# tmc2209.net
KiCad netlist of a schematic drawn in EAGLE
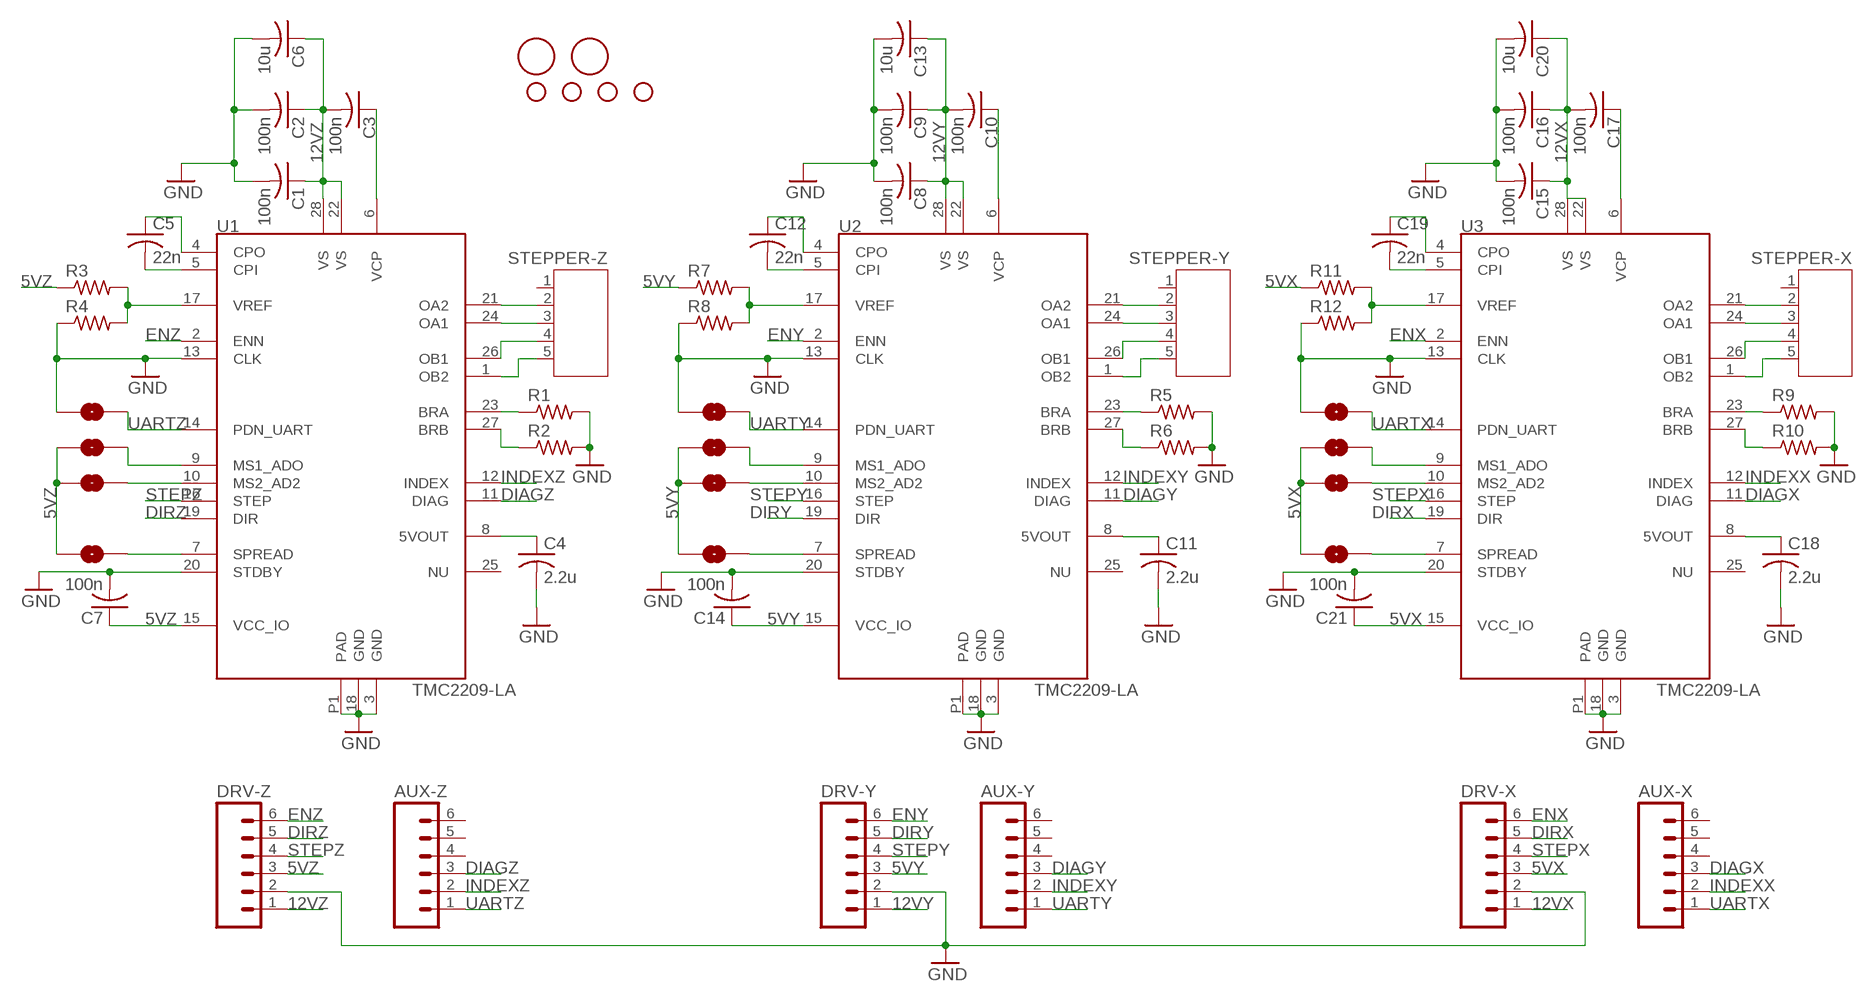
[diagram p0: schematic, sheet 1]

(export (version "E")
  (design (tool "Eeschema 10.0.6"))
  (components
    (comp (ref "AUX-X")
      (value "M06LOCK")
      (footprint "eagle-import:1X06_LOCK")
      (libsource (lib "eagle-import") (part "M06LOCK"))
    )
    (comp (ref "AUX-Y")
      (value "M06LOCK")
      (footprint "eagle-import:1X06_LOCK")
      (libsource (lib "eagle-import") (part "M06LOCK"))
    )
    (comp (ref "AUX-Z")
      (value "M06LOCK")
      (footprint "eagle-import:1X06_LOCK")
      (libsource (lib "eagle-import") (part "M06LOCK"))
    )
    (comp (ref "C1")
      (value "100n")
      (footprint "eagle-import:C0603")
      (libsource (lib "eagle-import") (part "C-USC0603"))
    )
    (comp (ref "C2")
      (value "100n")
      (footprint "eagle-import:C0603")
      (libsource (lib "eagle-import") (part "C-USC0603"))
    )
    (comp (ref "C3")
      (value "100n")
      (footprint "eagle-import:C0603")
      (libsource (lib "eagle-import") (part "C-USC0603"))
    )
    (comp (ref "C4")
      (value "2.2u")
      (footprint "eagle-import:C1206")
      (libsource (lib "eagle-import") (part "C-USC1206"))
    )
    (comp (ref "C5")
      (value "22n")
      (footprint "eagle-import:C0603")
      (libsource (lib "eagle-import") (part "C-USC0603"))
    )
    (comp (ref "C6")
      (value "10u")
      (footprint "eagle-import:C1206")
      (libsource (lib "eagle-import") (part "C-USC1206"))
    )
    (comp (ref "C7")
      (value "100n")
      (footprint "eagle-import:C0603")
      (libsource (lib "eagle-import") (part "C-USC0603"))
    )
    (comp (ref "C8")
      (value "100n")
      (footprint "eagle-import:C0603")
      (libsource (lib "eagle-import") (part "C-USC0603"))
    )
    (comp (ref "C9")
      (value "100n")
      (footprint "eagle-import:C0603")
      (libsource (lib "eagle-import") (part "C-USC0603"))
    )
    (comp (ref "C10")
      (value "100n")
      (footprint "eagle-import:C0603")
      (libsource (lib "eagle-import") (part "C-USC0603"))
    )
    (comp (ref "C11")
      (value "2.2u")
      (footprint "eagle-import:C1206")
      (libsource (lib "eagle-import") (part "C-USC1206"))
    )
    (comp (ref "C12")
      (value "22n")
      (footprint "eagle-import:C0603")
      (libsource (lib "eagle-import") (part "C-USC0603"))
    )
    (comp (ref "C13")
      (value "10u")
      (footprint "eagle-import:C1206")
      (libsource (lib "eagle-import") (part "C-USC1206"))
    )
    (comp (ref "C14")
      (value "100n")
      (footprint "eagle-import:C0603")
      (libsource (lib "eagle-import") (part "C-USC0603"))
    )
    (comp (ref "C15")
      (value "100n")
      (footprint "eagle-import:C0603")
      (libsource (lib "eagle-import") (part "C-USC0603"))
    )
    (comp (ref "C16")
      (value "100n")
      (footprint "eagle-import:C0603")
      (libsource (lib "eagle-import") (part "C-USC0603"))
    )
    (comp (ref "C17")
      (value "100n")
      (footprint "eagle-import:C0603")
      (libsource (lib "eagle-import") (part "C-USC0603"))
    )
    (comp (ref "C18")
      (value "2.2u")
      (footprint "eagle-import:C1206")
      (libsource (lib "eagle-import") (part "C-USC1206"))
    )
    (comp (ref "C19")
      (value "22n")
      (footprint "eagle-import:C0603")
      (libsource (lib "eagle-import") (part "C-USC0603"))
    )
    (comp (ref "C20")
      (value "10u")
      (footprint "eagle-import:C1206")
      (libsource (lib "eagle-import") (part "C-USC1206"))
    )
    (comp (ref "C21")
      (value "100n")
      (footprint "eagle-import:C0603")
      (libsource (lib "eagle-import") (part "C-USC0603"))
    )
    (comp (ref "DRV-X")
      (value "M06LOCK")
      (footprint "eagle-import:1X06_LOCK")
      (libsource (lib "eagle-import") (part "M06LOCK"))
    )
    (comp (ref "DRV-Y")
      (value "M06LOCK")
      (footprint "eagle-import:1X06_LOCK")
      (libsource (lib "eagle-import") (part "M06LOCK"))
    )
    (comp (ref "DRV-Z")
      (value "M06LOCK")
      (footprint "eagle-import:1X06_LOCK")
      (libsource (lib "eagle-import") (part "M06LOCK"))
    )
    (comp (ref "PDX")
      (value "SOLDERJUMPERNO")
      (footprint "eagle-import:SJ_2S-NO")
      (libsource (lib "eagle-import") (part "SOLDERJUMPERNO"))
    )
    (comp (ref "PDY")
      (value "SOLDERJUMPERNO")
      (footprint "eagle-import:SJ_2S-NO")
      (libsource (lib "eagle-import") (part "SOLDERJUMPERNO"))
    )
    (comp (ref "PDZ")
      (value "SOLDERJUMPERNO")
      (footprint "eagle-import:SJ_2S-NO")
      (libsource (lib "eagle-import") (part "SOLDERJUMPERNO"))
    )
    (comp (ref "R1")
      (value "R-US_R0805")
      (footprint "eagle-import:R0805")
      (libsource (lib "eagle-import") (part "R-US_R0805"))
    )
    (comp (ref "R2")
      (value "R-US_R0805")
      (footprint "eagle-import:R0805")
      (libsource (lib "eagle-import") (part "R-US_R0805"))
    )
    (comp (ref "R3")
      (value "R-US_R0603")
      (footprint "eagle-import:R0603")
      (libsource (lib "eagle-import") (part "R-US_R0603"))
    )
    (comp (ref "R4")
      (value "R-US_R0603")
      (footprint "eagle-import:R0603")
      (libsource (lib "eagle-import") (part "R-US_R0603"))
    )
    (comp (ref "R5")
      (value "R-US_R0805")
      (footprint "eagle-import:R0805")
      (libsource (lib "eagle-import") (part "R-US_R0805"))
    )
    (comp (ref "R6")
      (value "R-US_R0805")
      (footprint "eagle-import:R0805")
      (libsource (lib "eagle-import") (part "R-US_R0805"))
    )
    (comp (ref "R7")
      (value "R-US_R0603")
      (footprint "eagle-import:R0603")
      (libsource (lib "eagle-import") (part "R-US_R0603"))
    )
    (comp (ref "R8")
      (value "R-US_R0603")
      (footprint "eagle-import:R0603")
      (libsource (lib "eagle-import") (part "R-US_R0603"))
    )
    (comp (ref "R9")
      (value "R-US_R0805")
      (footprint "eagle-import:R0805")
      (libsource (lib "eagle-import") (part "R-US_R0805"))
    )
    (comp (ref "R10")
      (value "R-US_R0805")
      (footprint "eagle-import:R0805")
      (libsource (lib "eagle-import") (part "R-US_R0805"))
    )
    (comp (ref "R11")
      (value "R-US_R0603")
      (footprint "eagle-import:R0603")
      (libsource (lib "eagle-import") (part "R-US_R0603"))
    )
    (comp (ref "R12")
      (value "R-US_R0603")
      (footprint "eagle-import:R0603")
      (libsource (lib "eagle-import") (part "R-US_R0603"))
    )
    (comp (ref "SJ2")
      (value "SOLDERJUMPERNO")
      (footprint "eagle-import:SJ_2S-NO")
      (libsource (lib "eagle-import") (part "SOLDERJUMPERNO"))
    )
    (comp (ref "SJ3")
      (value "SOLDERJUMPERNO")
      (footprint "eagle-import:SJ_2S-NO")
      (libsource (lib "eagle-import") (part "SOLDERJUMPERNO"))
    )
    (comp (ref "SJ5")
      (value "SOLDERJUMPERNO")
      (footprint "eagle-import:SJ_2S-NO")
      (libsource (lib "eagle-import") (part "SOLDERJUMPERNO"))
    )
    (comp (ref "SJ6")
      (value "SOLDERJUMPERNO")
      (footprint "eagle-import:SJ_2S-NO")
      (libsource (lib "eagle-import") (part "SOLDERJUMPERNO"))
    )
    (comp (ref "SJ8")
      (value "SOLDERJUMPERNO")
      (footprint "eagle-import:SJ_2S-NO")
      (libsource (lib "eagle-import") (part "SOLDERJUMPERNO"))
    )
    (comp (ref "SJ9")
      (value "SOLDERJUMPERNO")
      (footprint "eagle-import:SJ_2S-NO")
      (libsource (lib "eagle-import") (part "SOLDERJUMPERNO"))
    )
    (comp (ref "SJ10")
      (value "SOLDERJUMPERNO")
      (footprint "eagle-import:SJ_2S-NO")
      (libsource (lib "eagle-import") (part "SOLDERJUMPERNO"))
    )
    (comp (ref "SJ11")
      (value "SOLDERJUMPERNO")
      (footprint "eagle-import:SJ_2S-NO")
      (libsource (lib "eagle-import") (part "SOLDERJUMPERNO"))
    )
    (comp (ref "SJ12")
      (value "SOLDERJUMPERNO")
      (footprint "eagle-import:SJ_2S-NO")
      (libsource (lib "eagle-import") (part "SOLDERJUMPERNO"))
    )
    (comp (ref "STANDOFF1")
      (value "STAND-OFFTIGHT")
      (footprint "eagle-import:STAND-OFF-TIGHT")
      (libsource (lib "eagle-import") (part "STAND-OFFTIGHT"))
    )
    (comp (ref "STANDOFF2")
      (value "STAND-OFFTIGHT")
      (footprint "eagle-import:STAND-OFF-TIGHT")
      (libsource (lib "eagle-import") (part "STAND-OFFTIGHT"))
    )
    (comp (ref "STANDOFF3")
      (value "STAND-OFFTIGHT")
      (footprint "eagle-import:STAND-OFF-TIGHT")
      (libsource (lib "eagle-import") (part "STAND-OFFTIGHT"))
    )
    (comp (ref "STANDOFF4")
      (value "STAND-OFFTIGHT")
      (footprint "eagle-import:STAND-OFF-TIGHT")
      (libsource (lib "eagle-import") (part "STAND-OFFTIGHT"))
    )
    (comp (ref "STEPPER-X")
      (value "JST-PH5")
      (footprint "eagle-import:JST-PH5")
      (libsource (lib "eagle-import") (part "JST-PH5"))
    )
    (comp (ref "STEPPER-Y")
      (value "JST-PH5")
      (footprint "eagle-import:JST-PH5")
      (libsource (lib "eagle-import") (part "JST-PH5"))
    )
    (comp (ref "STEPPER-Z")
      (value "JST-PH5")
      (footprint "eagle-import:JST-PH5")
      (libsource (lib "eagle-import") (part "JST-PH5"))
    )
    (comp (ref "U$1")
      (value "FIDUCIAL")
      (footprint "eagle-import:FIDUCIAL_1MM")
      (libsource (lib "eagle-import") (part "FIDUCIAL"))
    )
    (comp (ref "U$2")
      (value "FIDUCIAL")
      (footprint "eagle-import:FIDUCIAL_1MM")
      (libsource (lib "eagle-import") (part "FIDUCIAL"))
    )
    (comp (ref "U1")
      (value "TMC2209-LA")
      (footprint "eagle-import:QFN28-5X5-XLEP")
      (libsource (lib "eagle-import") (part "TMC2209-LA"))
    )
    (comp (ref "U2")
      (value "TMC2209-LA")
      (footprint "eagle-import:QFN28-5X5-XLEP")
      (libsource (lib "eagle-import") (part "TMC2209-LA"))
    )
    (comp (ref "U3")
      (value "TMC2209-LA")
      (footprint "eagle-import:QFN28-5X5-XLEP")
      (libsource (lib "eagle-import") (part "TMC2209-LA"))
    )
  )
  (nets
    (net (code "1") (name "/5VX") (class "Default")
      (node (ref "C21") (pin "1") (pinfunction "1_1") (pintype "passive"))
      (node (ref "DRV-X") (pin "3") (pinfunction "3_3") (pintype "passive"))
      (node (ref "R11") (pin "1") (pinfunction "1_1") (pintype "passive"))
      (node (ref "SJ12") (pin "1") (pinfunction "1_1") (pintype "passive"))
      (node (ref "SJ8") (pin "1") (pinfunction "1_1") (pintype "passive"))
      (node (ref "SJ9") (pin "1") (pinfunction "1_1") (pintype "passive"))
      (node (ref "U3") (pin "15") (pinfunction "VCC_IO_15") (pintype "bidirectional"))
    )
    (net (code "2") (name "/5VY") (class "Default")
      (node (ref "C14") (pin "1") (pinfunction "1_1") (pintype "passive"))
      (node (ref "DRV-Y") (pin "3") (pinfunction "3_3") (pintype "passive"))
      (node (ref "R7") (pin "1") (pinfunction "1_1") (pintype "passive"))
      (node (ref "SJ11") (pin "1") (pinfunction "1_1") (pintype "passive"))
      (node (ref "SJ5") (pin "1") (pinfunction "1_1") (pintype "passive"))
      (node (ref "SJ6") (pin "1") (pinfunction "1_1") (pintype "passive"))
      (node (ref "U2") (pin "15") (pinfunction "VCC_IO_15") (pintype "bidirectional"))
    )
    (net (code "3") (name "/5VZ") (class "Default")
      (node (ref "C7") (pin "1") (pinfunction "1_1") (pintype "passive"))
      (node (ref "DRV-Z") (pin "3") (pinfunction "3_3") (pintype "passive"))
      (node (ref "R3") (pin "1") (pinfunction "1_1") (pintype "passive"))
      (node (ref "SJ10") (pin "1") (pinfunction "1_1") (pintype "passive"))
      (node (ref "SJ2") (pin "1") (pinfunction "1_1") (pintype "passive"))
      (node (ref "SJ3") (pin "1") (pinfunction "1_1") (pintype "passive"))
      (node (ref "U1") (pin "15") (pinfunction "VCC_IO_15") (pintype "bidirectional"))
    )
    (net (code "4") (name "/12VX") (class "Default")
      (node (ref "C15") (pin "1") (pinfunction "1_1") (pintype "passive"))
      (node (ref "C16") (pin "1") (pinfunction "1_1") (pintype "passive"))
      (node (ref "C17") (pin "2") (pinfunction "2_2") (pintype "passive"))
      (node (ref "C20") (pin "1") (pinfunction "1_1") (pintype "passive"))
      (node (ref "DRV-X") (pin "1") (pinfunction "1_1") (pintype "passive"))
      (node (ref "U3") (pin "22") (pinfunction "VS_22") (pintype "bidirectional"))
      (node (ref "U3") (pin "28") (pinfunction "VS_28") (pintype "bidirectional"))
    )
    (net (code "5") (name "/12VY") (class "Default")
      (node (ref "C10") (pin "2") (pinfunction "2_2") (pintype "passive"))
      (node (ref "C13") (pin "1") (pinfunction "1_1") (pintype "passive"))
      (node (ref "C8") (pin "1") (pinfunction "1_1") (pintype "passive"))
      (node (ref "C9") (pin "1") (pinfunction "1_1") (pintype "passive"))
      (node (ref "DRV-Y") (pin "1") (pinfunction "1_1") (pintype "passive"))
      (node (ref "U2") (pin "22") (pinfunction "VS_22") (pintype "bidirectional"))
      (node (ref "U2") (pin "28") (pinfunction "VS_28") (pintype "bidirectional"))
    )
    (net (code "6") (name "/12VZ") (class "Default")
      (node (ref "C1") (pin "1") (pinfunction "1_1") (pintype "passive"))
      (node (ref "C2") (pin "1") (pinfunction "1_1") (pintype "passive"))
      (node (ref "C3") (pin "2") (pinfunction "2_2") (pintype "passive"))
      (node (ref "C6") (pin "1") (pinfunction "1_1") (pintype "passive"))
      (node (ref "DRV-Z") (pin "1") (pinfunction "1_1") (pintype "passive"))
      (node (ref "U1") (pin "22") (pinfunction "VS_22") (pintype "bidirectional"))
      (node (ref "U1") (pin "28") (pinfunction "VS_28") (pintype "bidirectional"))
    )
    (net (code "7") (name "/DIAGX") (class "Default")
      (node (ref "AUX-X") (pin "3") (pinfunction "3_3") (pintype "passive"))
      (node (ref "U3") (pin "11") (pinfunction "DIAG_11") (pintype "bidirectional"))
    )
    (net (code "8") (name "/DIAGY") (class "Default")
      (node (ref "AUX-Y") (pin "3") (pinfunction "3_3") (pintype "passive"))
      (node (ref "U2") (pin "11") (pinfunction "DIAG_11") (pintype "bidirectional"))
    )
    (net (code "9") (name "/DIAGZ") (class "Default")
      (node (ref "AUX-Z") (pin "3") (pinfunction "3_3") (pintype "passive"))
      (node (ref "U1") (pin "11") (pinfunction "DIAG_11") (pintype "bidirectional"))
    )
    (net (code "10") (name "/DIRX") (class "Default")
      (node (ref "DRV-X") (pin "5") (pinfunction "5_5") (pintype "passive"))
      (node (ref "U3") (pin "19") (pinfunction "DIR_19") (pintype "bidirectional"))
    )
    (net (code "11") (name "/DIRY") (class "Default")
      (node (ref "DRV-Y") (pin "5") (pinfunction "5_5") (pintype "passive"))
      (node (ref "U2") (pin "19") (pinfunction "DIR_19") (pintype "bidirectional"))
    )
    (net (code "12") (name "/DIRZ") (class "Default")
      (node (ref "DRV-Z") (pin "5") (pinfunction "5_5") (pintype "passive"))
      (node (ref "U1") (pin "19") (pinfunction "DIR_19") (pintype "bidirectional"))
    )
    (net (code "13") (name "/ENX") (class "Default")
      (node (ref "DRV-X") (pin "6") (pinfunction "6_6") (pintype "passive"))
      (node (ref "U3") (pin "2") (pinfunction "ENN_2") (pintype "bidirectional"))
    )
    (net (code "14") (name "/ENY") (class "Default")
      (node (ref "DRV-Y") (pin "6") (pinfunction "6_6") (pintype "passive"))
      (node (ref "U2") (pin "2") (pinfunction "ENN_2") (pintype "bidirectional"))
    )
    (net (code "15") (name "/ENZ") (class "Default")
      (node (ref "DRV-Z") (pin "6") (pinfunction "6_6") (pintype "passive"))
      (node (ref "U1") (pin "2") (pinfunction "ENN_2") (pintype "bidirectional"))
    )
    (net (code "16") (name "/INDEXX") (class "Default")
      (node (ref "AUX-X") (pin "2") (pinfunction "2_2") (pintype "passive"))
      (node (ref "U3") (pin "12") (pinfunction "INDEX_12") (pintype "bidirectional"))
    )
    (net (code "17") (name "/INDEXY") (class "Default")
      (node (ref "AUX-Y") (pin "2") (pinfunction "2_2") (pintype "passive"))
      (node (ref "U2") (pin "12") (pinfunction "INDEX_12") (pintype "bidirectional"))
    )
    (net (code "18") (name "/INDEXZ") (class "Default")
      (node (ref "AUX-Z") (pin "2") (pinfunction "2_2") (pintype "passive"))
      (node (ref "U1") (pin "12") (pinfunction "INDEX_12") (pintype "bidirectional"))
    )
    (net (code "19") (name "/STEPX") (class "Default")
      (node (ref "DRV-X") (pin "4") (pinfunction "4_4") (pintype "passive"))
      (node (ref "U3") (pin "16") (pinfunction "STEP_16") (pintype "bidirectional"))
    )
    (net (code "20") (name "/STEPY") (class "Default")
      (node (ref "DRV-Y") (pin "4") (pinfunction "4_4") (pintype "passive"))
      (node (ref "U2") (pin "16") (pinfunction "STEP_16") (pintype "bidirectional"))
    )
    (net (code "21") (name "/STEPZ") (class "Default")
      (node (ref "DRV-Z") (pin "4") (pinfunction "4_4") (pintype "passive"))
      (node (ref "U1") (pin "16") (pinfunction "STEP_16") (pintype "bidirectional"))
    )
    (net (code "22") (name "/UARTX") (class "Default")
      (node (ref "AUX-X") (pin "1") (pinfunction "1_1") (pintype "passive"))
      (node (ref "PDX") (pin "2") (pinfunction "2_2") (pintype "passive"))
      (node (ref "U3") (pin "14") (pinfunction "PDN_UART_14") (pintype "bidirectional"))
    )
    (net (code "23") (name "/UARTY") (class "Default")
      (node (ref "AUX-Y") (pin "1") (pinfunction "1_1") (pintype "passive"))
      (node (ref "PDY") (pin "2") (pinfunction "2_2") (pintype "passive"))
      (node (ref "U2") (pin "14") (pinfunction "PDN_UART_14") (pintype "bidirectional"))
    )
    (net (code "24") (name "/UARTZ") (class "Default")
      (node (ref "AUX-Z") (pin "1") (pinfunction "1_1") (pintype "passive"))
      (node (ref "PDZ") (pin "2") (pinfunction "2_2") (pintype "passive"))
      (node (ref "U1") (pin "14") (pinfunction "PDN_UART_14") (pintype "bidirectional"))
    )
    (net (code "25") (name "GND") (class "Default")
      (node (ref "C1") (pin "2") (pinfunction "2_2") (pintype "passive"))
      (node (ref "C11") (pin "2") (pinfunction "2_2") (pintype "passive"))
      (node (ref "C13") (pin "2") (pinfunction "2_2") (pintype "passive"))
      (node (ref "C14") (pin "2") (pinfunction "2_2") (pintype "passive"))
      (node (ref "C15") (pin "2") (pinfunction "2_2") (pintype "passive"))
      (node (ref "C16") (pin "2") (pinfunction "2_2") (pintype "passive"))
      (node (ref "C18") (pin "2") (pinfunction "2_2") (pintype "passive"))
      (node (ref "C2") (pin "2") (pinfunction "2_2") (pintype "passive"))
      (node (ref "C20") (pin "2") (pinfunction "2_2") (pintype "passive"))
      (node (ref "C21") (pin "2") (pinfunction "2_2") (pintype "passive"))
      (node (ref "C4") (pin "2") (pinfunction "2_2") (pintype "passive"))
      (node (ref "C6") (pin "2") (pinfunction "2_2") (pintype "passive"))
      (node (ref "C7") (pin "2") (pinfunction "2_2") (pintype "passive"))
      (node (ref "C8") (pin "2") (pinfunction "2_2") (pintype "passive"))
      (node (ref "C9") (pin "2") (pinfunction "2_2") (pintype "passive"))
      (node (ref "DRV-X") (pin "2") (pinfunction "2_2") (pintype "passive"))
      (node (ref "DRV-Y") (pin "2") (pinfunction "2_2") (pintype "passive"))
      (node (ref "DRV-Z") (pin "2") (pinfunction "2_2") (pintype "passive"))
      (node (ref "PDX") (pin "1") (pinfunction "1_1") (pintype "passive"))
      (node (ref "PDY") (pin "1") (pinfunction "1_1") (pintype "passive"))
      (node (ref "PDZ") (pin "1") (pinfunction "1_1") (pintype "passive"))
      (node (ref "R1") (pin "2") (pinfunction "2_2") (pintype "passive"))
      (node (ref "R10") (pin "2") (pinfunction "2_2") (pintype "passive"))
      (node (ref "R12") (pin "1") (pinfunction "1_1") (pintype "passive"))
      (node (ref "R2") (pin "2") (pinfunction "2_2") (pintype "passive"))
      (node (ref "R4") (pin "1") (pinfunction "1_1") (pintype "passive"))
      (node (ref "R5") (pin "2") (pinfunction "2_2") (pintype "passive"))
      (node (ref "R6") (pin "2") (pinfunction "2_2") (pintype "passive"))
      (node (ref "R8") (pin "1") (pinfunction "1_1") (pintype "passive"))
      (node (ref "R9") (pin "2") (pinfunction "2_2") (pintype "passive"))
      (node (ref "U1") (pin "13") (pinfunction "CLK_13") (pintype "bidirectional"))
      (node (ref "U1") (pin "18") (pinfunction "GND_18") (pintype "bidirectional"))
      (node (ref "U1") (pin "20") (pinfunction "STDBY_20") (pintype "bidirectional"))
      (node (ref "U1") (pin "3") (pinfunction "GND_3") (pintype "bidirectional"))
      (node (ref "U1") (pin "P1") (pinfunction "PAD_P1") (pintype "bidirectional"))
      (node (ref "U2") (pin "13") (pinfunction "CLK_13") (pintype "bidirectional"))
      (node (ref "U2") (pin "18") (pinfunction "GND_18") (pintype "bidirectional"))
      (node (ref "U2") (pin "20") (pinfunction "STDBY_20") (pintype "bidirectional"))
      (node (ref "U2") (pin "3") (pinfunction "GND_3") (pintype "bidirectional"))
      (node (ref "U2") (pin "P1") (pinfunction "PAD_P1") (pintype "bidirectional"))
      (node (ref "U3") (pin "13") (pinfunction "CLK_13") (pintype "bidirectional"))
      (node (ref "U3") (pin "18") (pinfunction "GND_18") (pintype "bidirectional"))
      (node (ref "U3") (pin "20") (pinfunction "STDBY_20") (pintype "bidirectional"))
      (node (ref "U3") (pin "3") (pinfunction "GND_3") (pintype "bidirectional"))
      (node (ref "U3") (pin "P1") (pinfunction "PAD_P1") (pintype "bidirectional"))
    )
    (net (code "26") (name "Net-(U1-5VOUT)") (class "Default")
      (node (ref "C4") (pin "1") (pinfunction "1_1") (pintype "passive"))
      (node (ref "U1") (pin "8") (pinfunction "5VOUT_8") (pintype "bidirectional"))
    )
    (net (code "27") (name "Net-(U1-BRA)") (class "Default")
      (node (ref "R1") (pin "1") (pinfunction "1_1") (pintype "passive"))
      (node (ref "U1") (pin "23") (pinfunction "BRA_23") (pintype "bidirectional"))
    )
    (net (code "28") (name "Net-(U1-BRB)") (class "Default")
      (node (ref "R2") (pin "1") (pinfunction "1_1") (pintype "passive"))
      (node (ref "U1") (pin "27") (pinfunction "BRB_27") (pintype "bidirectional"))
    )
    (net (code "29") (name "Net-(U1-CPI)") (class "Default")
      (node (ref "C5") (pin "2") (pinfunction "2_2") (pintype "passive"))
      (node (ref "U1") (pin "5") (pinfunction "CPI_5") (pintype "bidirectional"))
    )
    (net (code "30") (name "Net-(U1-CPO)") (class "Default")
      (node (ref "C5") (pin "1") (pinfunction "1_1") (pintype "passive"))
      (node (ref "U1") (pin "4") (pinfunction "CPO_4") (pintype "bidirectional"))
    )
    (net (code "31") (name "Net-(U1-MS1_ADO)") (class "Default")
      (node (ref "SJ2") (pin "2") (pinfunction "2_2") (pintype "passive"))
      (node (ref "U1") (pin "9") (pinfunction "MS1_ADO_9") (pintype "bidirectional"))
    )
    (net (code "32") (name "Net-(U1-MS2_AD2)") (class "Default")
      (node (ref "SJ3") (pin "2") (pinfunction "2_2") (pintype "passive"))
      (node (ref "U1") (pin "10") (pinfunction "MS2_AD2_10") (pintype "bidirectional"))
    )
    (net (code "33") (name "Net-(U1-OA1)") (class "Default")
      (node (ref "STEPPER-Z") (pin "3") (pinfunction "3_3") (pintype "passive"))
      (node (ref "U1") (pin "24") (pinfunction "OA1_24") (pintype "bidirectional"))
    )
    (net (code "34") (name "Net-(U1-OA2)") (class "Default")
      (node (ref "STEPPER-Z") (pin "2") (pinfunction "2_2") (pintype "passive"))
      (node (ref "U1") (pin "21") (pinfunction "OA2_21") (pintype "bidirectional"))
    )
    (net (code "35") (name "Net-(U1-OB1)") (class "Default")
      (node (ref "STEPPER-Z") (pin "4") (pinfunction "4_4") (pintype "passive"))
      (node (ref "U1") (pin "26") (pinfunction "OB1_26") (pintype "bidirectional"))
    )
    (net (code "36") (name "Net-(U1-OB2)") (class "Default")
      (node (ref "STEPPER-Z") (pin "5") (pinfunction "5_5") (pintype "passive"))
      (node (ref "U1") (pin "1") (pinfunction "OB2_1") (pintype "bidirectional"))
    )
    (net (code "37") (name "Net-(U1-SPREAD)") (class "Default")
      (node (ref "SJ10") (pin "2") (pinfunction "2_2") (pintype "passive"))
      (node (ref "U1") (pin "7") (pinfunction "SPREAD_7") (pintype "bidirectional"))
    )
    (net (code "38") (name "Net-(U1-VCP)") (class "Default")
      (node (ref "C3") (pin "1") (pinfunction "1_1") (pintype "passive"))
      (node (ref "U1") (pin "6") (pinfunction "VCP_6") (pintype "bidirectional"))
    )
    (net (code "39") (name "Net-(U1-VREF)") (class "Default")
      (node (ref "R3") (pin "2") (pinfunction "2_2") (pintype "passive"))
      (node (ref "R4") (pin "2") (pinfunction "2_2") (pintype "passive"))
      (node (ref "U1") (pin "17") (pinfunction "VREF_17") (pintype "bidirectional"))
    )
    (net (code "40") (name "Net-(U2-5VOUT)") (class "Default")
      (node (ref "C11") (pin "1") (pinfunction "1_1") (pintype "passive"))
      (node (ref "U2") (pin "8") (pinfunction "5VOUT_8") (pintype "bidirectional"))
    )
    (net (code "41") (name "Net-(U2-BRA)") (class "Default")
      (node (ref "R5") (pin "1") (pinfunction "1_1") (pintype "passive"))
      (node (ref "U2") (pin "23") (pinfunction "BRA_23") (pintype "bidirectional"))
    )
    (net (code "42") (name "Net-(U2-BRB)") (class "Default")
      (node (ref "R6") (pin "1") (pinfunction "1_1") (pintype "passive"))
      (node (ref "U2") (pin "27") (pinfunction "BRB_27") (pintype "bidirectional"))
    )
    (net (code "43") (name "Net-(U2-CPI)") (class "Default")
      (node (ref "C12") (pin "2") (pinfunction "2_2") (pintype "passive"))
      (node (ref "U2") (pin "5") (pinfunction "CPI_5") (pintype "bidirectional"))
    )
    (net (code "44") (name "Net-(U2-CPO)") (class "Default")
      (node (ref "C12") (pin "1") (pinfunction "1_1") (pintype "passive"))
      (node (ref "U2") (pin "4") (pinfunction "CPO_4") (pintype "bidirectional"))
    )
    (net (code "45") (name "Net-(U2-MS1_ADO)") (class "Default")
      (node (ref "SJ5") (pin "2") (pinfunction "2_2") (pintype "passive"))
      (node (ref "U2") (pin "9") (pinfunction "MS1_ADO_9") (pintype "bidirectional"))
    )
    (net (code "46") (name "Net-(U2-MS2_AD2)") (class "Default")
      (node (ref "SJ6") (pin "2") (pinfunction "2_2") (pintype "passive"))
      (node (ref "U2") (pin "10") (pinfunction "MS2_AD2_10") (pintype "bidirectional"))
    )
    (net (code "47") (name "Net-(U2-OA1)") (class "Default")
      (node (ref "STEPPER-Y") (pin "3") (pinfunction "3_3") (pintype "passive"))
      (node (ref "U2") (pin "24") (pinfunction "OA1_24") (pintype "bidirectional"))
    )
    (net (code "48") (name "Net-(U2-OA2)") (class "Default")
      (node (ref "STEPPER-Y") (pin "2") (pinfunction "2_2") (pintype "passive"))
      (node (ref "U2") (pin "21") (pinfunction "OA2_21") (pintype "bidirectional"))
    )
    (net (code "49") (name "Net-(U2-OB1)") (class "Default")
      (node (ref "STEPPER-Y") (pin "4") (pinfunction "4_4") (pintype "passive"))
      (node (ref "U2") (pin "26") (pinfunction "OB1_26") (pintype "bidirectional"))
    )
    (net (code "50") (name "Net-(U2-OB2)") (class "Default")
      (node (ref "STEPPER-Y") (pin "5") (pinfunction "5_5") (pintype "passive"))
      (node (ref "U2") (pin "1") (pinfunction "OB2_1") (pintype "bidirectional"))
    )
    (net (code "51") (name "Net-(U2-SPREAD)") (class "Default")
      (node (ref "SJ11") (pin "2") (pinfunction "2_2") (pintype "passive"))
      (node (ref "U2") (pin "7") (pinfunction "SPREAD_7") (pintype "bidirectional"))
    )
    (net (code "52") (name "Net-(U2-VCP)") (class "Default")
      (node (ref "C10") (pin "1") (pinfunction "1_1") (pintype "passive"))
      (node (ref "U2") (pin "6") (pinfunction "VCP_6") (pintype "bidirectional"))
    )
    (net (code "53") (name "Net-(U2-VREF)") (class "Default")
      (node (ref "R7") (pin "2") (pinfunction "2_2") (pintype "passive"))
      (node (ref "R8") (pin "2") (pinfunction "2_2") (pintype "passive"))
      (node (ref "U2") (pin "17") (pinfunction "VREF_17") (pintype "bidirectional"))
    )
    (net (code "54") (name "Net-(U3-5VOUT)") (class "Default")
      (node (ref "C18") (pin "1") (pinfunction "1_1") (pintype "passive"))
      (node (ref "U3") (pin "8") (pinfunction "5VOUT_8") (pintype "bidirectional"))
    )
    (net (code "55") (name "Net-(U3-BRA)") (class "Default")
      (node (ref "R9") (pin "1") (pinfunction "1_1") (pintype "passive"))
      (node (ref "U3") (pin "23") (pinfunction "BRA_23") (pintype "bidirectional"))
    )
    (net (code "56") (name "Net-(U3-BRB)") (class "Default")
      (node (ref "R10") (pin "1") (pinfunction "1_1") (pintype "passive"))
      (node (ref "U3") (pin "27") (pinfunction "BRB_27") (pintype "bidirectional"))
    )
    (net (code "57") (name "Net-(U3-CPI)") (class "Default")
      (node (ref "C19") (pin "2") (pinfunction "2_2") (pintype "passive"))
      (node (ref "U3") (pin "5") (pinfunction "CPI_5") (pintype "bidirectional"))
    )
    (net (code "58") (name "Net-(U3-CPO)") (class "Default")
      (node (ref "C19") (pin "1") (pinfunction "1_1") (pintype "passive"))
      (node (ref "U3") (pin "4") (pinfunction "CPO_4") (pintype "bidirectional"))
    )
    (net (code "59") (name "Net-(U3-MS1_ADO)") (class "Default")
      (node (ref "SJ8") (pin "2") (pinfunction "2_2") (pintype "passive"))
      (node (ref "U3") (pin "9") (pinfunction "MS1_ADO_9") (pintype "bidirectional"))
    )
    (net (code "60") (name "Net-(U3-MS2_AD2)") (class "Default")
      (node (ref "SJ9") (pin "2") (pinfunction "2_2") (pintype "passive"))
      (node (ref "U3") (pin "10") (pinfunction "MS2_AD2_10") (pintype "bidirectional"))
    )
    (net (code "61") (name "Net-(U3-OA1)") (class "Default")
      (node (ref "STEPPER-X") (pin "3") (pinfunction "3_3") (pintype "passive"))
      (node (ref "U3") (pin "24") (pinfunction "OA1_24") (pintype "bidirectional"))
    )
    (net (code "62") (name "Net-(U3-OA2)") (class "Default")
      (node (ref "STEPPER-X") (pin "2") (pinfunction "2_2") (pintype "passive"))
      (node (ref "U3") (pin "21") (pinfunction "OA2_21") (pintype "bidirectional"))
    )
    (net (code "63") (name "Net-(U3-OB1)") (class "Default")
      (node (ref "STEPPER-X") (pin "4") (pinfunction "4_4") (pintype "passive"))
      (node (ref "U3") (pin "26") (pinfunction "OB1_26") (pintype "bidirectional"))
    )
    (net (code "64") (name "Net-(U3-OB2)") (class "Default")
      (node (ref "STEPPER-X") (pin "5") (pinfunction "5_5") (pintype "passive"))
      (node (ref "U3") (pin "1") (pinfunction "OB2_1") (pintype "bidirectional"))
    )
    (net (code "65") (name "Net-(U3-SPREAD)") (class "Default")
      (node (ref "SJ12") (pin "2") (pinfunction "2_2") (pintype "passive"))
      (node (ref "U3") (pin "7") (pinfunction "SPREAD_7") (pintype "bidirectional"))
    )
    (net (code "66") (name "Net-(U3-VCP)") (class "Default")
      (node (ref "C17") (pin "1") (pinfunction "1_1") (pintype "passive"))
      (node (ref "U3") (pin "6") (pinfunction "VCP_6") (pintype "bidirectional"))
    )
    (net (code "67") (name "Net-(U3-VREF)") (class "Default")
      (node (ref "R11") (pin "2") (pinfunction "2_2") (pintype "passive"))
      (node (ref "R12") (pin "2") (pinfunction "2_2") (pintype "passive"))
      (node (ref "U3") (pin "17") (pinfunction "VREF_17") (pintype "bidirectional"))
    )
    (net (code "68") (name "unconnected-(AUX-X-Pad4)") (class "Default")
      (node (ref "AUX-X") (pin "4") (pinfunction "4_4") (pintype "passive"))
    )
    (net (code "69") (name "unconnected-(AUX-X-Pad5)") (class "Default")
      (node (ref "AUX-X") (pin "5") (pinfunction "5_5") (pintype "passive"))
    )
    (net (code "70") (name "unconnected-(AUX-X-Pad6)") (class "Default")
      (node (ref "AUX-X") (pin "6") (pinfunction "6_6") (pintype "passive"))
    )
    (net (code "71") (name "unconnected-(AUX-Y-Pad4)") (class "Default")
      (node (ref "AUX-Y") (pin "4") (pinfunction "4_4") (pintype "passive"))
    )
    (net (code "72") (name "unconnected-(AUX-Y-Pad5)") (class "Default")
      (node (ref "AUX-Y") (pin "5") (pinfunction "5_5") (pintype "passive"))
    )
    (net (code "73") (name "unconnected-(AUX-Y-Pad6)") (class "Default")
      (node (ref "AUX-Y") (pin "6") (pinfunction "6_6") (pintype "passive"))
    )
    (net (code "74") (name "unconnected-(AUX-Z-Pad4)") (class "Default")
      (node (ref "AUX-Z") (pin "4") (pinfunction "4_4") (pintype "passive"))
    )
    (net (code "75") (name "unconnected-(AUX-Z-Pad5)") (class "Default")
      (node (ref "AUX-Z") (pin "5") (pinfunction "5_5") (pintype "passive"))
    )
    (net (code "76") (name "unconnected-(AUX-Z-Pad6)") (class "Default")
      (node (ref "AUX-Z") (pin "6") (pinfunction "6_6") (pintype "passive"))
    )
    (net (code "77") (name "unconnected-(STEPPER-X-Pad1)") (class "Default")
      (node (ref "STEPPER-X") (pin "1") (pinfunction "1_1") (pintype "passive"))
    )
    (net (code "78") (name "unconnected-(STEPPER-Y-Pad1)") (class "Default")
      (node (ref "STEPPER-Y") (pin "1") (pinfunction "1_1") (pintype "passive"))
    )
    (net (code "79") (name "unconnected-(STEPPER-Z-Pad1)") (class "Default")
      (node (ref "STEPPER-Z") (pin "1") (pinfunction "1_1") (pintype "passive"))
    )
    (net (code "80") (name "unconnected-(U1-NU-Pad25)") (class "Default")
      (node (ref "U1") (pin "25") (pinfunction "NU_25") (pintype "bidirectional"))
    )
    (net (code "81") (name "unconnected-(U2-NU-Pad25)") (class "Default")
      (node (ref "U2") (pin "25") (pinfunction "NU_25") (pintype "bidirectional"))
    )
    (net (code "82") (name "unconnected-(U3-NU-Pad25)") (class "Default")
      (node (ref "U3") (pin "25") (pinfunction "NU_25") (pintype "bidirectional"))
    )
  )
)
